# BMS.net
KiCad netlist of a schematic drawn in Altium Designer
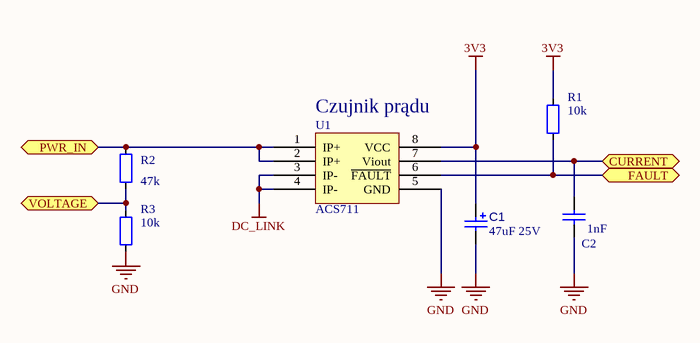
[diagram p0: BMS.SchDoc]

(export (version "E")
  (design (tool "Eeschema 10.0.6"))
  (components
    (comp (ref "C1")
      (value "47uF 25V")
      (footprint "Con_SMD_5x5.5")
      (description "Polar capacitor")
      (libsource (lib "Library_Altium_KNR") (part "Cap_Pol"))
    )
    (comp (ref "C2")
      (value "1nF")
      (footprint "0603_CAP")
      (description "Ceramic capacitor")
      (libsource (lib "Library_Altium_KNR") (part "Cap"))
    )
    (comp (ref "R1")
      (value "10k")
      (footprint "0603")
      (description "Resistior")
      (libsource (lib "Library_Altium_KNR") (part "RES"))
    )
    (comp (ref "R2")
      (value "47k")
      (footprint "0603")
      (description "Resistior")
      (libsource (lib "Library_Altium_KNR") (part "RES"))
    )
    (comp (ref "R3")
      (value "10k")
      (footprint "0603")
      (description "Resistior")
      (libsource (lib "Library_Altium_KNR") (part "RES"))
    )
    (comp (ref "U1")
      (value "ACS711")
      (footprint "Library_Altium_KNR:SO-8_N")
      (description "Current sensor. 12.5A or 25A at 3.3V")
      (fields
        (field (name "HELPURL") "C:\\Users\\micha\\Documents\\Studia\\Inżynierka\\Elektronika\\Datasheets\\ACS711.pdf")
      )
      (libsource (lib "Library_Altium_KNR") (part "ACS711"))
    )
  )
  (nets
    (net (code "1") (name "/CURRENT") (class "Default")
      (node (ref "C2") (pin "2") (pinfunction "2_2") (pintype "passive"))
      (node (ref "U1") (pin "7") (pinfunction "Viout_7") (pintype "passive"))
    )
    (net (code "2") (name "/FAULT") (class "Default")
      (node (ref "R1") (pin "1") (pinfunction "1_1") (pintype "passive"))
      (node (ref "U1") (pin "6") (pinfunction "~{FAULT}_6") (pintype "passive"))
    )
    (net (code "3") (name "/PWR_IN") (class "Default")
      (node (ref "R2") (pin "2") (pinfunction "2_2") (pintype "passive"))
      (node (ref "U1") (pin "1") (pinfunction "IP+_1") (pintype "passive"))
      (node (ref "U1") (pin "2") (pinfunction "IP+_2") (pintype "passive"))
    )
    (net (code "4") (name "/VOLTAGE") (class "Default")
      (node (ref "R2") (pin "1") (pinfunction "1_1") (pintype "passive"))
      (node (ref "R3") (pin "2") (pinfunction "2_2") (pintype "passive"))
    )
    (net (code "5") (name "3V3") (class "Default")
      (node (ref "C1") (pin "1") (pinfunction "1_1") (pintype "passive"))
      (node (ref "R1") (pin "2") (pinfunction "2_2") (pintype "passive"))
      (node (ref "U1") (pin "8") (pinfunction "VCC_8") (pintype "passive"))
    )
    (net (code "6") (name "DC_LINK") (class "Default")
      (node (ref "U1") (pin "3") (pinfunction "IP-_3") (pintype "passive"))
      (node (ref "U1") (pin "4") (pinfunction "IP-_4") (pintype "passive"))
    )
    (net (code "7") (name "GND") (class "Default")
      (node (ref "C1") (pin "2") (pinfunction "2_2") (pintype "passive"))
      (node (ref "C2") (pin "1") (pinfunction "1_1") (pintype "passive"))
      (node (ref "R3") (pin "1") (pinfunction "1_1") (pintype "passive"))
      (node (ref "U1") (pin "5") (pinfunction "GND_5") (pintype "passive"))
    )
  )
)
